# ModTeensy.net
KiCad netlist of a schematic drawn in Altium Designer
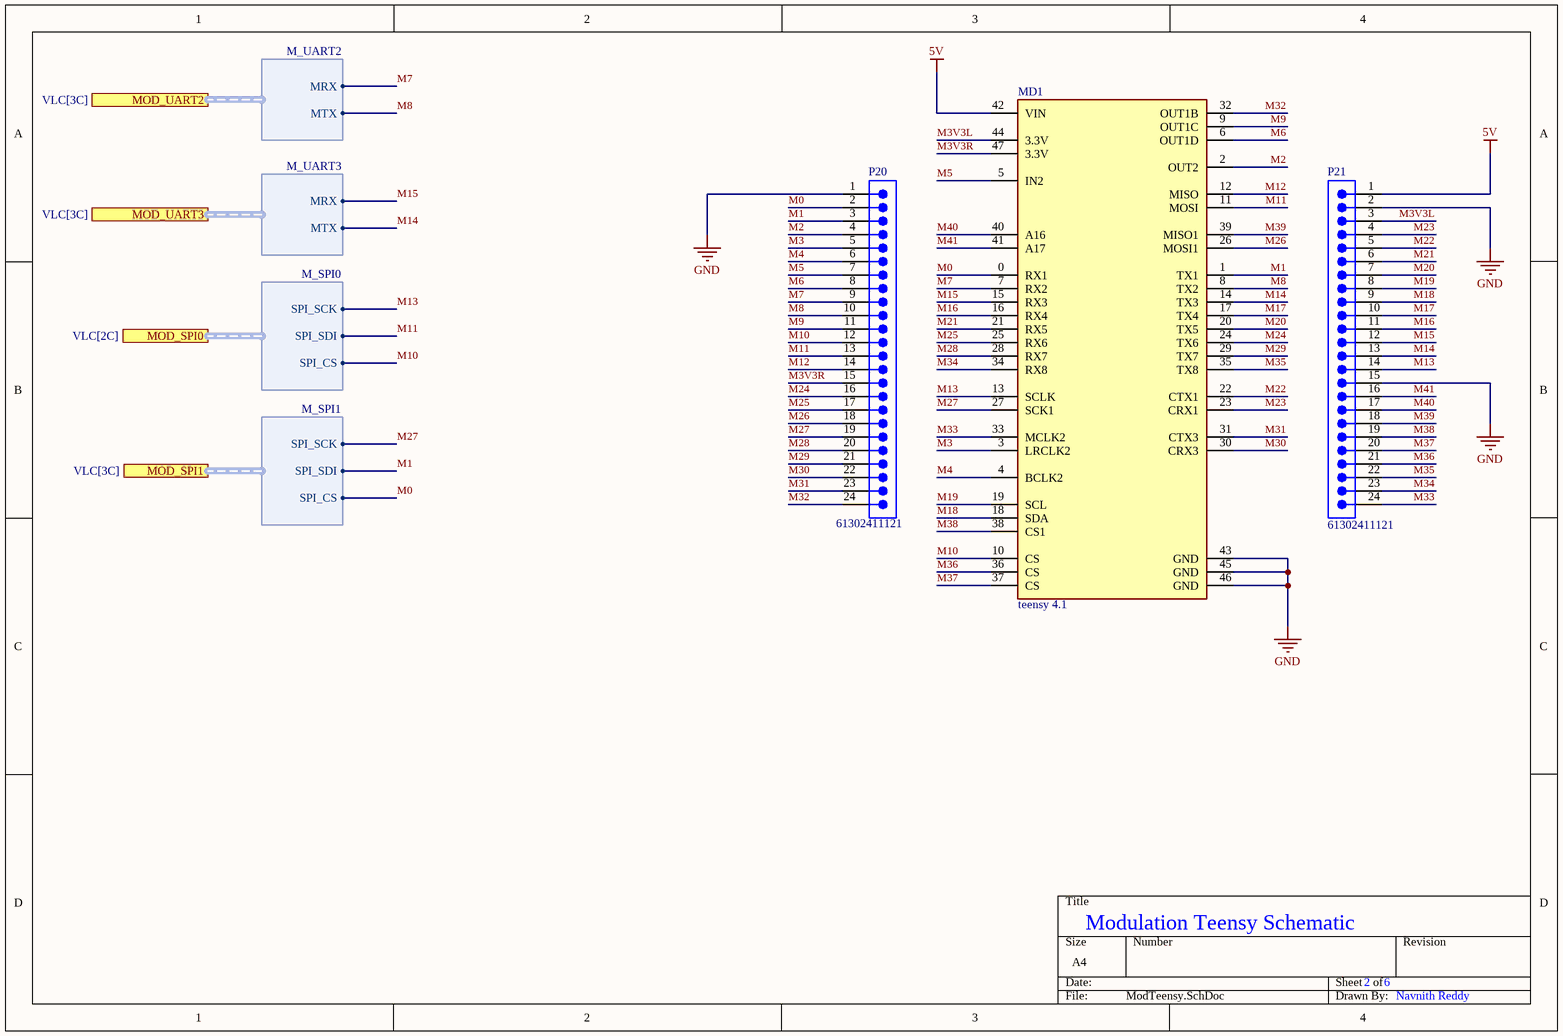
[diagram p0: ModTeensy.SchDoc]

(export (version "E")
  (design (tool "Eeschema 10.0.6"))
  (components
    (comp (ref "MD1")
      (value "teensy 4.1")
      (footprint "FP-DEV-16996-MFG")
      (description "TEENSY 4.1 (HEADERS)")
      (libsource (lib "Altium Content Vault") (part "080115a1ce54750370cf87ec145ee29"))
    )
    (comp (ref "P20")
      (value "61302411121")
      (footprint "61302411121")
      (libsource (lib "Altium Content Vault") (part "Header_Male_1R_24P"))
    )
    (comp (ref "P21")
      (value "61302411121")
      (footprint "61302411121")
      (libsource (lib "Altium Content Vault") (part "Header_Male_1R_24P"))
    )
  )
  (nets
    (net (code "5") (name "/M0") (class "Default")
      (node (ref "MD1") (pin "0") (pinfunction "RX1_0") (pintype "passive"))
      (node (ref "P20") (pin "2") (pinfunction "2_2") (pintype "passive"))
    )
    (net (code "6") (name "/M1") (class "Default")
      (node (ref "MD1") (pin "1") (pinfunction "TX1_1") (pintype "passive"))
      (node (ref "P20") (pin "3") (pinfunction "3_3") (pintype "passive"))
    )
    (net (code "7") (name "/M2") (class "Default")
      (node (ref "MD1") (pin "2") (pinfunction "OUT2_2") (pintype "passive"))
      (node (ref "P20") (pin "4") (pinfunction "4_4") (pintype "passive"))
    )
    (net (code "8") (name "/M3") (class "Default")
      (node (ref "MD1") (pin "3") (pinfunction "LRCLK2_3") (pintype "passive"))
      (node (ref "P20") (pin "5") (pinfunction "5_5") (pintype "passive"))
    )
    (net (code "9") (name "/M3V3L") (class "Default")
      (node (ref "MD1") (pin "44") (pinfunction "3.3V_44") (pintype "passive"))
      (node (ref "P21") (pin "3") (pinfunction "3_3") (pintype "passive"))
    )
    (net (code "10") (name "/M3V3R") (class "Default")
      (node (ref "MD1") (pin "47") (pinfunction "3.3V_47") (pintype "passive"))
      (node (ref "P20") (pin "15") (pinfunction "15_15") (pintype "passive"))
    )
    (net (code "11") (name "/M4") (class "Default")
      (node (ref "MD1") (pin "4") (pinfunction "BCLK2_4") (pintype "passive"))
      (node (ref "P20") (pin "6") (pinfunction "6_6") (pintype "passive"))
    )
    (net (code "12") (name "/M5") (class "Default")
      (node (ref "MD1") (pin "5") (pinfunction "IN2_5") (pintype "passive"))
      (node (ref "P20") (pin "7") (pinfunction "7_7") (pintype "passive"))
    )
    (net (code "13") (name "/M6") (class "Default")
      (node (ref "MD1") (pin "6") (pinfunction "OUT1D_6") (pintype "passive"))
      (node (ref "P20") (pin "8") (pinfunction "8_8") (pintype "passive"))
    )
    (net (code "14") (name "/M7") (class "Default")
      (node (ref "MD1") (pin "7") (pinfunction "RX2_7") (pintype "passive"))
      (node (ref "P20") (pin "9") (pinfunction "9_9") (pintype "passive"))
    )
    (net (code "15") (name "/M8") (class "Default")
      (node (ref "MD1") (pin "8") (pinfunction "TX2_8") (pintype "passive"))
      (node (ref "P20") (pin "10") (pinfunction "10_10") (pintype "passive"))
    )
    (net (code "16") (name "/M9") (class "Default")
      (node (ref "MD1") (pin "9") (pinfunction "OUT1C_9") (pintype "passive"))
      (node (ref "P20") (pin "11") (pinfunction "11_11") (pintype "passive"))
    )
    (net (code "17") (name "/M10") (class "Default")
      (node (ref "MD1") (pin "10") (pinfunction "CS_10") (pintype "passive"))
      (node (ref "P20") (pin "12") (pinfunction "12_12") (pintype "passive"))
    )
    (net (code "18") (name "/M11") (class "Default")
      (node (ref "MD1") (pin "11") (pinfunction "MOSI_11") (pintype "passive"))
      (node (ref "P20") (pin "13") (pinfunction "13_13") (pintype "passive"))
    )
    (net (code "19") (name "/M12") (class "Default")
      (node (ref "MD1") (pin "12") (pinfunction "MISO_12") (pintype "passive"))
      (node (ref "P20") (pin "14") (pinfunction "14_14") (pintype "passive"))
    )
    (net (code "20") (name "/M13") (class "Default")
      (node (ref "MD1") (pin "13") (pinfunction "SCLK_13") (pintype "passive"))
      (node (ref "P21") (pin "14") (pinfunction "14_14") (pintype "passive"))
    )
    (net (code "21") (name "/M14") (class "Default")
      (node (ref "MD1") (pin "14") (pinfunction "TX3_14") (pintype "passive"))
      (node (ref "P21") (pin "13") (pinfunction "13_13") (pintype "passive"))
    )
    (net (code "22") (name "/M15") (class "Default")
      (node (ref "MD1") (pin "15") (pinfunction "RX3_15") (pintype "passive"))
      (node (ref "P21") (pin "12") (pinfunction "12_12") (pintype "passive"))
    )
    (net (code "23") (name "/M16") (class "Default")
      (node (ref "MD1") (pin "16") (pinfunction "RX4_16") (pintype "passive"))
      (node (ref "P21") (pin "11") (pinfunction "11_11") (pintype "passive"))
    )
    (net (code "24") (name "/M17") (class "Default")
      (node (ref "MD1") (pin "17") (pinfunction "TX4_17") (pintype "passive"))
      (node (ref "P21") (pin "10") (pinfunction "10_10") (pintype "passive"))
    )
    (net (code "25") (name "/M18") (class "Default")
      (node (ref "MD1") (pin "18") (pinfunction "SDA_18") (pintype "passive"))
      (node (ref "P21") (pin "9") (pinfunction "9_9") (pintype "passive"))
    )
    (net (code "26") (name "/M19") (class "Default")
      (node (ref "MD1") (pin "19") (pinfunction "SCL_19") (pintype "passive"))
      (node (ref "P21") (pin "8") (pinfunction "8_8") (pintype "passive"))
    )
    (net (code "27") (name "/M20") (class "Default")
      (node (ref "MD1") (pin "20") (pinfunction "TX5_20") (pintype "passive"))
      (node (ref "P21") (pin "7") (pinfunction "7_7") (pintype "passive"))
    )
    (net (code "28") (name "/M21") (class "Default")
      (node (ref "MD1") (pin "21") (pinfunction "RX5_21") (pintype "passive"))
      (node (ref "P21") (pin "6") (pinfunction "6_6") (pintype "passive"))
    )
    (net (code "29") (name "/M22") (class "Default")
      (node (ref "MD1") (pin "22") (pinfunction "CTX1_22") (pintype "passive"))
      (node (ref "P21") (pin "5") (pinfunction "5_5") (pintype "passive"))
    )
    (net (code "30") (name "/M23") (class "Default")
      (node (ref "MD1") (pin "23") (pinfunction "CRX1_23") (pintype "passive"))
      (node (ref "P21") (pin "4") (pinfunction "4_4") (pintype "passive"))
    )
    (net (code "31") (name "/M24") (class "Default")
      (node (ref "MD1") (pin "24") (pinfunction "TX6_24") (pintype "passive"))
      (node (ref "P20") (pin "16") (pinfunction "16_16") (pintype "passive"))
    )
    (net (code "32") (name "/M25") (class "Default")
      (node (ref "MD1") (pin "25") (pinfunction "RX6_25") (pintype "passive"))
      (node (ref "P20") (pin "17") (pinfunction "17_17") (pintype "passive"))
    )
    (net (code "33") (name "/M26") (class "Default")
      (node (ref "MD1") (pin "26") (pinfunction "MOSI1_26") (pintype "passive"))
      (node (ref "P20") (pin "18") (pinfunction "18_18") (pintype "passive"))
    )
    (net (code "34") (name "/M27") (class "Default")
      (node (ref "MD1") (pin "27") (pinfunction "SCK1_27") (pintype "passive"))
      (node (ref "P20") (pin "19") (pinfunction "19_19") (pintype "passive"))
    )
    (net (code "35") (name "/M28") (class "Default")
      (node (ref "MD1") (pin "28") (pinfunction "RX7_28") (pintype "passive"))
      (node (ref "P20") (pin "20") (pinfunction "20_20") (pintype "passive"))
    )
    (net (code "36") (name "/M29") (class "Default")
      (node (ref "MD1") (pin "29") (pinfunction "TX7_29") (pintype "passive"))
      (node (ref "P20") (pin "21") (pinfunction "21_21") (pintype "passive"))
    )
    (net (code "37") (name "/M30") (class "Default")
      (node (ref "MD1") (pin "30") (pinfunction "CRX3_30") (pintype "passive"))
      (node (ref "P20") (pin "22") (pinfunction "22_22") (pintype "passive"))
    )
    (net (code "38") (name "/M31") (class "Default")
      (node (ref "MD1") (pin "31") (pinfunction "CTX3_31") (pintype "passive"))
      (node (ref "P20") (pin "23") (pinfunction "23_23") (pintype "passive"))
    )
    (net (code "39") (name "/M32") (class "Default")
      (node (ref "MD1") (pin "32") (pinfunction "OUT1B_32") (pintype "passive"))
      (node (ref "P20") (pin "24") (pinfunction "24_24") (pintype "passive"))
    )
    (net (code "40") (name "/M33") (class "Default")
      (node (ref "MD1") (pin "33") (pinfunction "MCLK2_33") (pintype "passive"))
      (node (ref "P21") (pin "24") (pinfunction "24_24") (pintype "passive"))
    )
    (net (code "41") (name "/M34") (class "Default")
      (node (ref "MD1") (pin "34") (pinfunction "RX8_34") (pintype "passive"))
      (node (ref "P21") (pin "23") (pinfunction "23_23") (pintype "passive"))
    )
    (net (code "42") (name "/M35") (class "Default")
      (node (ref "MD1") (pin "35") (pinfunction "TX8_35") (pintype "passive"))
      (node (ref "P21") (pin "22") (pinfunction "22_22") (pintype "passive"))
    )
    (net (code "43") (name "/M36") (class "Default")
      (node (ref "MD1") (pin "36") (pinfunction "CS_36") (pintype "passive"))
      (node (ref "P21") (pin "21") (pinfunction "21_21") (pintype "passive"))
    )
    (net (code "44") (name "/M37") (class "Default")
      (node (ref "MD1") (pin "37") (pinfunction "CS_37") (pintype "passive"))
      (node (ref "P21") (pin "20") (pinfunction "20_20") (pintype "passive"))
    )
    (net (code "45") (name "/M38") (class "Default")
      (node (ref "MD1") (pin "38") (pinfunction "CS1_38") (pintype "passive"))
      (node (ref "P21") (pin "19") (pinfunction "19_19") (pintype "passive"))
    )
    (net (code "46") (name "/M39") (class "Default")
      (node (ref "MD1") (pin "39") (pinfunction "MISO1_39") (pintype "passive"))
      (node (ref "P21") (pin "18") (pinfunction "18_18") (pintype "passive"))
    )
    (net (code "47") (name "/M40") (class "Default")
      (node (ref "MD1") (pin "40") (pinfunction "A16_40") (pintype "passive"))
      (node (ref "P21") (pin "17") (pinfunction "17_17") (pintype "passive"))
    )
    (net (code "48") (name "/M41") (class "Default")
      (node (ref "MD1") (pin "41") (pinfunction "A17_41") (pintype "passive"))
      (node (ref "P21") (pin "16") (pinfunction "16_16") (pintype "passive"))
    )
    (net (code "53") (name "5V") (class "Default")
      (node (ref "MD1") (pin "42") (pinfunction "VIN_42") (pintype "passive"))
      (node (ref "P21") (pin "1") (pinfunction "1_1") (pintype "passive"))
    )
    (net (code "54") (name "GND") (class "Default")
      (node (ref "MD1") (pin "43") (pinfunction "GND_43") (pintype "passive"))
      (node (ref "MD1") (pin "45") (pinfunction "GND_45") (pintype "passive"))
      (node (ref "MD1") (pin "46") (pinfunction "GND_46") (pintype "passive"))
      (node (ref "P20") (pin "1") (pinfunction "1_1") (pintype "passive"))
      (node (ref "P21") (pin "15") (pinfunction "15_15") (pintype "passive"))
      (node (ref "P21") (pin "2") (pinfunction "2_2") (pintype "passive"))
    )
  )
)
